# REF5050.net
KiCad netlist of a schematic drawn in Altium Designer
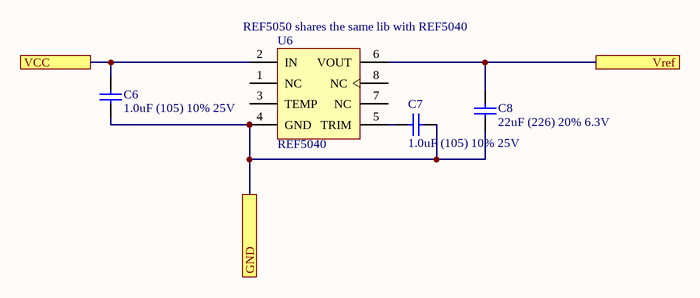
[diagram p0: REF5050.SchDoc]

(export (version "E")
  (design (tool "Eeschema 10.0.6"))
  (components
    (comp (ref "C6")
      (value "1.0uF (105) 10% 25V")
      (footprint "0402_C")
      (description "贴片电容")
      (libsource (lib "Miscellaneous Devices LC") (part "0402 1.0uF (105) 10% 25V"))
    )
    (comp (ref "C7")
      (value "1.0uF (105) 10% 25V")
      (footprint "0402_C")
      (description "贴片电容")
      (libsource (lib "Miscellaneous Devices LC") (part "0402 1.0uF (105) 10% 25V"))
    )
    (comp (ref "C8")
      (value "22uF (226) 20% 6.3V")
      (footprint "0603_C")
      (description "贴片电容")
      (libsource (lib "Miscellaneous Devices LC") (part "0603 22uF (226) 20% 6.3V"))
    )
    (comp (ref "U6")
      (value "REF5040")
      (footprint "SOP8_N")
      (description "高精度电压基准")
      (fields (field (name "版权归属") "源创客"))
      (libsource (lib "1.3   - 电源类芯片") (part "REF5040"))
    )
  )
  (nets
    (net (code "1") (name "/GND") (class "Default")
      (node (ref "C6") (pin "1") (pinfunction "1_1") (pintype "passive"))
      (node (ref "C7") (pin "2") (pinfunction "2_2") (pintype "passive"))
      (node (ref "C8") (pin "1") (pinfunction "1_1") (pintype "passive"))
      (node (ref "U6") (pin "4") (pinfunction "GND_4") (pintype "passive"))
    )
    (net (code "2") (name "/VCC") (class "Default")
      (node (ref "C6") (pin "2") (pinfunction "2_2") (pintype "passive"))
      (node (ref "U6") (pin "2") (pinfunction "IN_2") (pintype "passive"))
    )
    (net (code "3") (name "/Vref") (class "Default")
      (node (ref "C8") (pin "2") (pinfunction "2_2") (pintype "passive"))
      (node (ref "U6") (pin "6") (pinfunction "VOUT_6") (pintype "passive"))
    )
    (net (code "4") (name "Net-(U6-TRIM)") (class "Default")
      (node (ref "C7") (pin "1") (pinfunction "1_1") (pintype "passive"))
      (node (ref "U6") (pin "5") (pinfunction "TRIM_5") (pintype "passive"))
    )
    (net (code "5") (name "unconnected-(U6-NC-Pad1)") (class "Default")
      (node (ref "U6") (pin "1") (pinfunction "NC_1") (pintype "passive"))
    )
    (net (code "6") (name "unconnected-(U6-NC-Pad7)") (class "Default")
      (node (ref "U6") (pin "7") (pinfunction "NC_7") (pintype "passive"))
    )
    (net (code "7") (name "unconnected-(U6-NC-Pad8)") (class "Default")
      (node (ref "U6") (pin "8") (pinfunction "NC_8") (pintype "passive"))
    )
    (net (code "8") (name "unconnected-(U6-TEMP-Pad3)") (class "Default")
      (node (ref "U6") (pin "3") (pinfunction "TEMP_3") (pintype "passive"))
    )
  )
)
